# DM1092_Connector.net
KiCad netlist of a schematic drawn in Altium Designer
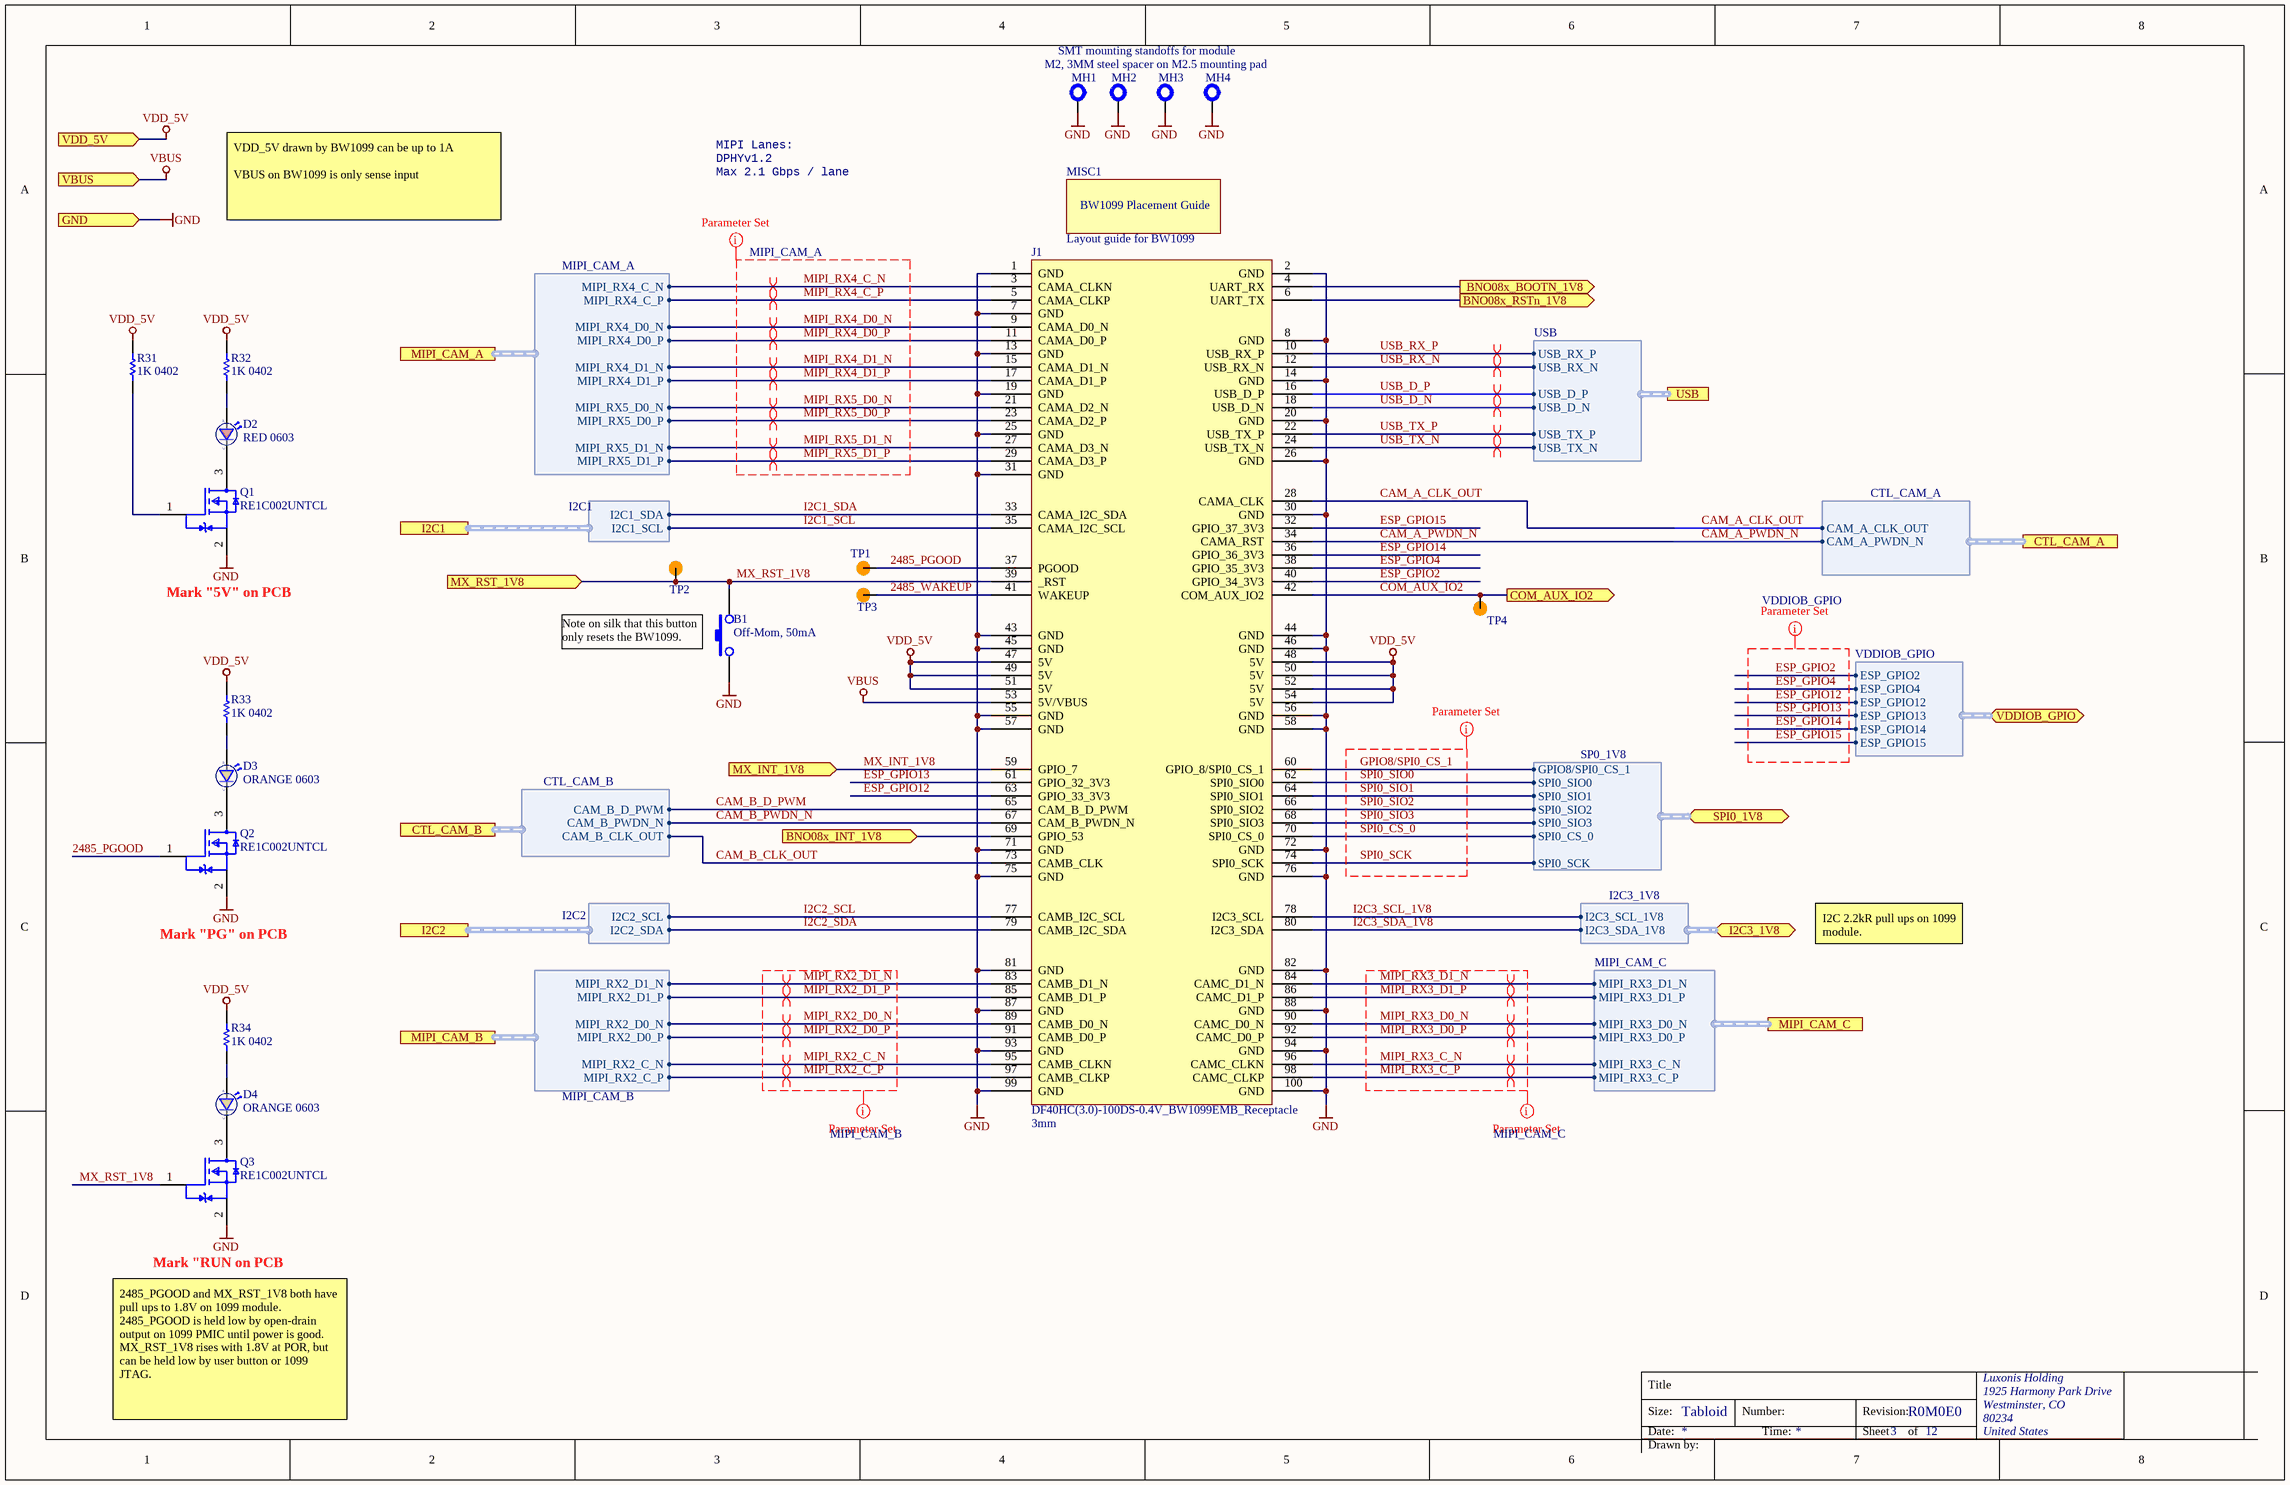
[diagram p0: DM1092_Connector.SchDoc]

(export (version "E")
  (design (tool "Eeschema 10.0.6"))
  (components
    (comp (ref "B1")
      (value "Off-Mom, 50mA")
      (footprint "LuxonisMaster:DTSM-32N-V")
      (description "SWITCH TACTILE SMT 3.5mm * 6mm , brown 160gf")
      (libsource (lib "LuxonisMaster") (part "DTSM-32N-V"))
    )
    (comp (ref "D2")
      (value "RED 0603")
      (footprint "LuxonisMaster:SML_D1xx8W")
      (description "LED RED DIFFUSED 0603 SMD Red 620nm LED Indication - Discrete 2.2V 0603 (1608 Metric)")
      (libsource (lib "LuxonisMaster") (part "SML-D12U8WT86"))
    )
    (comp (ref "D3")
      (value "ORANGE 0603")
      (footprint "LuxonisMaster:SML_D1xx8W")
      (description "LED ORANGE DIFFUSED 0603 SMD Orange 605nm LED Indication - Discrete 2.2V 0603 (1608 Metric)")
      (libsource (lib "LuxonisMaster") (part "SML-D12D8WT86"))
    )
    (comp (ref "D4")
      (value "ORANGE 0603")
      (footprint "LuxonisMaster:SML_D1xx8W")
      (description "LED ORANGE DIFFUSED 0603 SMD Orange 605nm LED Indication - Discrete 2.2V 0603 (1608 Metric)")
      (libsource (lib "LuxonisMaster") (part "SML-D12D8WT86"))
    )
    (comp (ref "J1")
      (value "DF40HC(3.0)-100DS-0.4V_BW1099EMB_Receptacle")
      (footprint "LuxonisMaster:DF40HC-3.0-100DS-0.4V_minpad")
      (description "CONN RCPT 100POS 0.4MM SMD GOLD EMB PINOUT")
      (fields (field (name "MATED STACKING HEIGHT") "3mm"))
      (libsource (lib "BW1098EMB_R0M0E0") (part "DF40HC(3.0)-100DS-0.4V_BW1099EMB"))
    )
    (comp (ref "MH1")
      (value "M2, 3MM steel spacer on M2.5 mounting pad")
      (footprint "LuxonisMaster:9774030243R")
      (description "MP ROUND STANDOFF M2X0.4 STEEL 3MM")
      (libsource (lib "LuxonisMaster") (part "9774030243R"))
    )
    (comp (ref "MH2")
      (value "M2, 3MM steel spacer on M2.5 mounting pad")
      (footprint "LuxonisMaster:9774030243R")
      (description "MP ROUND STANDOFF M2X0.4 STEEL 3MM")
      (libsource (lib "LuxonisMaster") (part "9774030243R"))
    )
    (comp (ref "MH3")
      (value "M2, 3MM steel spacer on M2.5 mounting pad")
      (footprint "LuxonisMaster:9774030243R")
      (description "MP ROUND STANDOFF M2X0.4 STEEL 3MM")
      (libsource (lib "LuxonisMaster") (part "9774030243R"))
    )
    (comp (ref "MH4")
      (value "M2, 3MM steel spacer on M2.5 mounting pad")
      (footprint "LuxonisMaster:9774030243R")
      (description "MP ROUND STANDOFF M2X0.4 STEEL 3MM")
      (libsource (lib "LuxonisMaster") (part "9774030243R"))
    )
    (comp (ref "MISC1")
      (value "Layout guide for BW1099")
      (footprint "BW1099_R3_KTHSNF_Footprint")
      (description "MISC - Use for aligning BW1099 mount")
      (libsource (lib "LuxonisMaster") (part "BW1099_Footprint"))
    )
    (comp (ref "Q1")
      (value "RE1C002UNTCL")
      (footprint "LuxonisMaster:RE1C002UNTCL")
      (description "MOSFET N-CH 20V 0.2A EMT3")
      (libsource (lib "LuxonisMaster") (part "RE1C002UNTCL"))
    )
    (comp (ref "Q2")
      (value "RE1C002UNTCL")
      (footprint "LuxonisMaster:RE1C002UNTCL")
      (description "MOSFET N-CH 20V 0.2A EMT3")
      (libsource (lib "LuxonisMaster") (part "RE1C002UNTCL"))
    )
    (comp (ref "Q3")
      (value "RE1C002UNTCL")
      (footprint "LuxonisMaster:RE1C002UNTCL")
      (description "MOSFET N-CH 20V 0.2A EMT3")
      (libsource (lib "LuxonisMaster") (part "RE1C002UNTCL"))
    )
    (comp (ref "R31")
      (value "1K 0402")
      (footprint "RES_Altium_Vault_Generic:RESC0402(1005)_L")
      (fields (field (name "TOLERANCE") "1%"))
      (libsource (lib "LuxonisMaster") (part "RC0402FR-071KL"))
    )
    (comp (ref "R32")
      (value "1K 0402")
      (footprint "RES_Altium_Vault_Generic:RESC0402(1005)_L")
      (fields (field (name "TOLERANCE") "1%"))
      (libsource (lib "LuxonisMaster") (part "RC0402FR-071KL"))
    )
    (comp (ref "R33")
      (value "1K 0402")
      (footprint "RES_Altium_Vault_Generic:RESC0402(1005)_L")
      (fields (field (name "TOLERANCE") "1%"))
      (libsource (lib "LuxonisMaster") (part "RC0402FR-071KL"))
    )
    (comp (ref "R34")
      (value "1K 0402")
      (footprint "RES_Altium_Vault_Generic:RESC0402(1005)_L")
      (fields (field (name "TOLERANCE") "1%"))
      (libsource (lib "LuxonisMaster") (part "RC0402FR-071KL"))
    )
    (comp (ref "TP1")
      (value "TP100_200_NS")
      (footprint "LuxonisMaster:TP100_200_NS")
      (libsource (lib "LuxonisMaster") (part "TEST_POINT"))
    )
    (comp (ref "TP2")
      (value "TP100_200_NS")
      (footprint "LuxonisMaster:TP100_200_NS")
      (libsource (lib "LuxonisMaster") (part "TEST_POINT"))
    )
    (comp (ref "TP3")
      (value "TP100_200_NS")
      (footprint "LuxonisMaster:TP100_200_NS")
      (libsource (lib "LuxonisMaster") (part "TEST_POINT"))
    )
    (comp (ref "TP4")
      (value "TP100_200_NS")
      (footprint "LuxonisMaster:TP100_200_NS")
      (libsource (lib "LuxonisMaster") (part "TEST_POINT"))
    )
  )
  (nets
    (net (code "12") (name "/2485_PGOOD") (class "Default")
      (node (ref "J1") (pin "37") (pinfunction "PGOOD_37") (pintype "passive"))
      (node (ref "Q2") (pin "1") (pinfunction "Gate_1") (pintype "passive"))
      (node (ref "TP1") (pin "1") (pintype "passive"))
    )
    (net (code "13") (name "/2485_WAKEUP") (class "Default")
      (node (ref "J1") (pin "41") (pinfunction "WAKEUP_41") (pintype "passive"))
      (node (ref "TP3") (pin "1") (pintype "passive"))
    )
    (net (code "14") (name "/BNO08x_BOOTN_1V8") (class "Default")
      (node (ref "J1") (pin "4") (pinfunction "UART_RX_4") (pintype "passive"))
    )
    (net (code "15") (name "/BNO08x_INT_1V8") (class "Default")
      (node (ref "J1") (pin "69") (pinfunction "GPIO_53_69") (pintype "passive"))
    )
    (net (code "16") (name "/BNO08x_RSTn_1V8") (class "Default")
      (node (ref "J1") (pin "6") (pinfunction "UART_TX_6") (pintype "passive"))
    )
    (net (code "17") (name "/CAM_A_CLK_OUT") (class "Default")
      (node (ref "J1") (pin "28") (pinfunction "CAMA_CLK_28") (pintype "passive"))
    )
    (net (code "18") (name "/CAM_A_PWDN_N") (class "Default")
      (node (ref "J1") (pin "34") (pinfunction "CAMA_RST_34") (pintype "passive"))
    )
    (net (code "19") (name "/CAM_B_CLK_OUT") (class "Default")
      (node (ref "J1") (pin "73") (pinfunction "CAMB_CLK_73") (pintype "passive"))
    )
    (net (code "20") (name "/CAM_B_D_PWM") (class "Default")
      (node (ref "J1") (pin "65") (pinfunction "CAM_B_D_PWM_65") (pintype "passive"))
    )
    (net (code "21") (name "/CAM_B_PWDN_N") (class "Default")
      (node (ref "J1") (pin "67") (pinfunction "CAM_B_PWDN_N_67") (pintype "passive"))
    )
    (net (code "22") (name "/COM_AUX_IO2") (class "Default")
      (node (ref "J1") (pin "42") (pinfunction "COM_AUX_IO2_42") (pintype "passive"))
      (node (ref "TP4") (pin "1") (pintype "passive"))
    )
    (net (code "23") (name "/ESP_GPIO2") (class "Default")
      (node (ref "J1") (pin "40") (pinfunction "GPIO_34_3V3_40") (pintype "passive"))
    )
    (net (code "24") (name "/ESP_GPIO4") (class "Default")
      (node (ref "J1") (pin "38") (pinfunction "GPIO_35_3V3_38") (pintype "passive"))
    )
    (net (code "25") (name "/ESP_GPIO12") (class "Default")
      (node (ref "J1") (pin "63") (pinfunction "GPIO_33_3V3_63") (pintype "passive"))
    )
    (net (code "26") (name "/ESP_GPIO13") (class "Default")
      (node (ref "J1") (pin "61") (pinfunction "GPIO_32_3V3_61") (pintype "passive"))
    )
    (net (code "27") (name "/ESP_GPIO14") (class "Default")
      (node (ref "J1") (pin "36") (pinfunction "GPIO_36_3V3_36") (pintype "passive"))
    )
    (net (code "28") (name "/ESP_GPIO15") (class "Default")
      (node (ref "J1") (pin "32") (pinfunction "GPIO_37_3V3_32") (pintype "passive"))
    )
    (net (code "29") (name "/GPIO8{slash}SPI0_CS_1") (class "Default")
      (node (ref "J1") (pin "60") (pinfunction "GPIO_8/SPI0_CS_1_60") (pintype "passive"))
    )
    (net (code "30") (name "/I2C1_SCL") (class "Default")
      (node (ref "J1") (pin "35") (pinfunction "CAMA_I2C_SCL_35") (pintype "passive"))
    )
    (net (code "31") (name "/I2C1_SDA") (class "Default")
      (node (ref "J1") (pin "33") (pinfunction "CAMA_I2C_SDA_33") (pintype "passive"))
    )
    (net (code "32") (name "/I2C2_SCL") (class "Default")
      (node (ref "J1") (pin "77") (pinfunction "CAMB_I2C_SCL_77") (pintype "passive"))
    )
    (net (code "33") (name "/I2C2_SDA") (class "Default")
      (node (ref "J1") (pin "79") (pinfunction "CAMB_I2C_SDA_79") (pintype "passive"))
    )
    (net (code "34") (name "/I2C3_SCL_1V8") (class "Default")
      (node (ref "J1") (pin "78") (pinfunction "I2C3_SCL_78") (pintype "passive"))
    )
    (net (code "35") (name "/I2C3_SDA_1V8") (class "Default")
      (node (ref "J1") (pin "80") (pinfunction "I2C3_SDA_80") (pintype "passive"))
    )
    (net (code "36") (name "/MIPI_RX2_C_N") (class "Default")
      (node (ref "J1") (pin "95") (pinfunction "CAMB_CLKN_95") (pintype "passive"))
    )
    (net (code "37") (name "/MIPI_RX2_C_P") (class "Default")
      (node (ref "J1") (pin "97") (pinfunction "CAMB_CLKP_97") (pintype "passive"))
    )
    (net (code "38") (name "/MIPI_RX2_D0_N") (class "Default")
      (node (ref "J1") (pin "89") (pinfunction "CAMB_D0_N_89") (pintype "passive"))
    )
    (net (code "39") (name "/MIPI_RX2_D0_P") (class "Default")
      (node (ref "J1") (pin "91") (pinfunction "CAMB_D0_P_91") (pintype "passive"))
    )
    (net (code "40") (name "/MIPI_RX2_D1_N") (class "Default")
      (node (ref "J1") (pin "83") (pinfunction "CAMB_D1_N_83") (pintype "passive"))
    )
    (net (code "41") (name "/MIPI_RX2_D1_P") (class "Default")
      (node (ref "J1") (pin "85") (pinfunction "CAMB_D1_P_85") (pintype "passive"))
    )
    (net (code "42") (name "/MIPI_RX3_C_N") (class "Default")
      (node (ref "J1") (pin "96") (pinfunction "CAMC_CLKN_96") (pintype "passive"))
    )
    (net (code "43") (name "/MIPI_RX3_C_P") (class "Default")
      (node (ref "J1") (pin "98") (pinfunction "CAMC_CLKP_98") (pintype "passive"))
    )
    (net (code "44") (name "/MIPI_RX3_D0_N") (class "Default")
      (node (ref "J1") (pin "90") (pinfunction "CAMC_D0_N_90") (pintype "passive"))
    )
    (net (code "45") (name "/MIPI_RX3_D0_P") (class "Default")
      (node (ref "J1") (pin "92") (pinfunction "CAMC_D0_P_92") (pintype "passive"))
    )
    (net (code "46") (name "/MIPI_RX3_D1_N") (class "Default")
      (node (ref "J1") (pin "84") (pinfunction "CAMC_D1_N_84") (pintype "passive"))
    )
    (net (code "47") (name "/MIPI_RX3_D1_P") (class "Default")
      (node (ref "J1") (pin "86") (pinfunction "CAMC_D1_P_86") (pintype "passive"))
    )
    (net (code "48") (name "/MIPI_RX4_C_N") (class "Default")
      (node (ref "J1") (pin "3") (pinfunction "CAMA_CLKN_3") (pintype "passive"))
    )
    (net (code "49") (name "/MIPI_RX4_C_P") (class "Default")
      (node (ref "J1") (pin "5") (pinfunction "CAMA_CLKP_5") (pintype "passive"))
    )
    (net (code "50") (name "/MIPI_RX4_D0_N") (class "Default")
      (node (ref "J1") (pin "9") (pinfunction "CAMA_D0_N_9") (pintype "passive"))
    )
    (net (code "51") (name "/MIPI_RX4_D0_P") (class "Default")
      (node (ref "J1") (pin "11") (pinfunction "CAMA_D0_P_11") (pintype "passive"))
    )
    (net (code "52") (name "/MIPI_RX4_D1_N") (class "Default")
      (node (ref "J1") (pin "15") (pinfunction "CAMA_D1_N_15") (pintype "passive"))
    )
    (net (code "53") (name "/MIPI_RX4_D1_P") (class "Default")
      (node (ref "J1") (pin "17") (pinfunction "CAMA_D1_P_17") (pintype "passive"))
    )
    (net (code "54") (name "/MIPI_RX5_D0_N") (class "Default")
      (node (ref "J1") (pin "21") (pinfunction "CAMA_D2_N_21") (pintype "passive"))
    )
    (net (code "55") (name "/MIPI_RX5_D0_P") (class "Default")
      (node (ref "J1") (pin "23") (pinfunction "CAMA_D2_P_23") (pintype "passive"))
    )
    (net (code "56") (name "/MIPI_RX5_D1_N") (class "Default")
      (node (ref "J1") (pin "27") (pinfunction "CAMA_D3_N_27") (pintype "passive"))
    )
    (net (code "57") (name "/MIPI_RX5_D1_P") (class "Default")
      (node (ref "J1") (pin "29") (pinfunction "CAMA_D3_P_29") (pintype "passive"))
    )
    (net (code "58") (name "/MX_INT_1V8") (class "Default")
      (node (ref "J1") (pin "59") (pinfunction "GPIO_7_59") (pintype "passive"))
    )
    (net (code "59") (name "/MX_RST_1V8") (class "Default")
      (node (ref "B1") (pin "2") (pinfunction "2_2") (pintype "passive"))
      (node (ref "J1") (pin "39") (pinfunction "_RST_39") (pintype "passive"))
      (node (ref "Q3") (pin "1") (pinfunction "Gate_1") (pintype "passive"))
      (node (ref "TP2") (pin "1") (pintype "passive"))
    )
    (net (code "60") (name "/SPI0_CS_0") (class "Default")
      (node (ref "J1") (pin "70") (pinfunction "SPI0_CS_0_70") (pintype "passive"))
    )
    (net (code "61") (name "/SPI0_SCK") (class "Default")
      (node (ref "J1") (pin "74") (pinfunction "SPI0_SCK_74") (pintype "passive"))
    )
    (net (code "62") (name "/SPI0_SIO0") (class "Default")
      (node (ref "J1") (pin "62") (pinfunction "SPI0_SIO0_62") (pintype "passive"))
    )
    (net (code "63") (name "/SPI0_SIO1") (class "Default")
      (node (ref "J1") (pin "64") (pinfunction "SPI0_SIO1_64") (pintype "passive"))
    )
    (net (code "64") (name "/SPI0_SIO2") (class "Default")
      (node (ref "J1") (pin "66") (pinfunction "SPI0_SIO2_66") (pintype "passive"))
    )
    (net (code "65") (name "/SPI0_SIO3") (class "Default")
      (node (ref "J1") (pin "68") (pinfunction "SPI0_SIO3_68") (pintype "passive"))
    )
    (net (code "66") (name "/USB_D_N") (class "Default")
      (node (ref "J1") (pin "18") (pinfunction "USB_D_N_18") (pintype "passive"))
    )
    (net (code "67") (name "/USB_D_P") (class "Default")
      (node (ref "J1") (pin "16") (pinfunction "USB_D_P_16") (pintype "passive"))
    )
    (net (code "68") (name "/USB_RX_N") (class "Default")
      (node (ref "J1") (pin "12") (pinfunction "USB_RX_N_12") (pintype "passive"))
    )
    (net (code "69") (name "/USB_RX_P") (class "Default")
      (node (ref "J1") (pin "10") (pinfunction "USB_RX_P_10") (pintype "passive"))
    )
    (net (code "70") (name "/USB_TX_N") (class "Default")
      (node (ref "J1") (pin "24") (pinfunction "USB_TX_N_24") (pintype "passive"))
    )
    (net (code "71") (name "/USB_TX_P") (class "Default")
      (node (ref "J1") (pin "22") (pinfunction "USB_TX_P_22") (pintype "passive"))
    )
    (net (code "83") (name "GND") (class "Default")
      (node (ref "B1") (pin "1") (pinfunction "1_1") (pintype "passive"))
      (node (ref "J1") (pin "1") (pinfunction "GND_1") (pintype "passive"))
      (node (ref "J1") (pin "100") (pinfunction "GND_100") (pintype "passive"))
      (node (ref "J1") (pin "13") (pinfunction "GND_13") (pintype "passive"))
      (node (ref "J1") (pin "14") (pinfunction "GND_14") (pintype "passive"))
      (node (ref "J1") (pin "19") (pinfunction "GND_19") (pintype "passive"))
      (node (ref "J1") (pin "2") (pinfunction "GND_2") (pintype "passive"))
      (node (ref "J1") (pin "20") (pinfunction "GND_20") (pintype "passive"))
      (node (ref "J1") (pin "25") (pinfunction "GND_25") (pintype "passive"))
      (node (ref "J1") (pin "26") (pinfunction "GND_26") (pintype "passive"))
      (node (ref "J1") (pin "30") (pinfunction "GND_30") (pintype "passive"))
      (node (ref "J1") (pin "31") (pinfunction "GND_31") (pintype "passive"))
      (node (ref "J1") (pin "43") (pinfunction "GND_43") (pintype "passive"))
      (node (ref "J1") (pin "44") (pinfunction "GND_44") (pintype "passive"))
      (node (ref "J1") (pin "45") (pinfunction "GND_45") (pintype "passive"))
      (node (ref "J1") (pin "46") (pinfunction "GND_46") (pintype "passive"))
      (node (ref "J1") (pin "55") (pinfunction "GND_55") (pintype "passive"))
      (node (ref "J1") (pin "56") (pinfunction "GND_56") (pintype "passive"))
      (node (ref "J1") (pin "57") (pinfunction "GND_57") (pintype "passive"))
      (node (ref "J1") (pin "58") (pinfunction "GND_58") (pintype "passive"))
      (node (ref "J1") (pin "7") (pinfunction "GND_7") (pintype "passive"))
      (node (ref "J1") (pin "71") (pinfunction "GND_71") (pintype "passive"))
      (node (ref "J1") (pin "72") (pinfunction "GND_72") (pintype "passive"))
      (node (ref "J1") (pin "75") (pinfunction "GND_75") (pintype "passive"))
      (node (ref "J1") (pin "76") (pinfunction "GND_76") (pintype "passive"))
      (node (ref "J1") (pin "8") (pinfunction "GND_8") (pintype "passive"))
      (node (ref "J1") (pin "81") (pinfunction "GND_81") (pintype "passive"))
      (node (ref "J1") (pin "82") (pinfunction "GND_82") (pintype "passive"))
      (node (ref "J1") (pin "87") (pinfunction "GND_87") (pintype "passive"))
      (node (ref "J1") (pin "88") (pinfunction "GND_88") (pintype "passive"))
      (node (ref "J1") (pin "93") (pinfunction "GND_93") (pintype "passive"))
      (node (ref "J1") (pin "94") (pinfunction "GND_94") (pintype "passive"))
      (node (ref "J1") (pin "99") (pinfunction "GND_99") (pintype "passive"))
      (node (ref "MH1") (pin "1") (pintype "passive"))
      (node (ref "MH2") (pin "1") (pintype "passive"))
      (node (ref "MH3") (pin "1") (pintype "passive"))
      (node (ref "MH4") (pin "1") (pintype "passive"))
      (node (ref "Q1") (pin "2") (pinfunction "Source_2") (pintype "passive"))
      (node (ref "Q2") (pin "2") (pinfunction "Source_2") (pintype "passive"))
      (node (ref "Q3") (pin "2") (pinfunction "Source_2") (pintype "passive"))
    )
    (net (code "84") (name "Net-(D2-A)") (class "Default")
      (node (ref "D2") (pin "2") (pinfunction "A_2") (pintype "passive"))
      (node (ref "R32") (pin "1") (pinfunction "1_1") (pintype "passive"))
    )
    (net (code "85") (name "Net-(D2-C)") (class "Default")
      (node (ref "D2") (pin "1") (pinfunction "C_1") (pintype "passive"))
      (node (ref "Q1") (pin "3") (pinfunction "Drain_3") (pintype "passive"))
    )
    (net (code "86") (name "Net-(D3-A)") (class "Default")
      (node (ref "D3") (pin "2") (pinfunction "A_2") (pintype "passive"))
      (node (ref "R33") (pin "1") (pinfunction "1_1") (pintype "passive"))
    )
    (net (code "87") (name "Net-(D3-C)") (class "Default")
      (node (ref "D3") (pin "1") (pinfunction "C_1") (pintype "passive"))
      (node (ref "Q2") (pin "3") (pinfunction "Drain_3") (pintype "passive"))
    )
    (net (code "88") (name "Net-(D4-A)") (class "Default")
      (node (ref "D4") (pin "2") (pinfunction "A_2") (pintype "passive"))
      (node (ref "R34") (pin "1") (pinfunction "1_1") (pintype "passive"))
    )
    (net (code "89") (name "Net-(D4-C)") (class "Default")
      (node (ref "D4") (pin "1") (pinfunction "C_1") (pintype "passive"))
      (node (ref "Q3") (pin "3") (pinfunction "Drain_3") (pintype "passive"))
    )
    (net (code "90") (name "Net-(Q1-Gate)") (class "Default")
      (node (ref "Q1") (pin "1") (pinfunction "Gate_1") (pintype "passive"))
      (node (ref "R31") (pin "1") (pinfunction "1_1") (pintype "passive"))
    )
    (net (code "91") (name "VBUS") (class "Default")
      (node (ref "J1") (pin "53") (pinfunction "5V/VBUS_53") (pintype "passive"))
    )
    (net (code "92") (name "VDD_5V") (class "Default")
      (node (ref "J1") (pin "47") (pinfunction "5V_47") (pintype "passive"))
      (node (ref "J1") (pin "48") (pinfunction "5V_48") (pintype "passive"))
      (node (ref "J1") (pin "49") (pinfunction "5V_49") (pintype "passive"))
      (node (ref "J1") (pin "50") (pinfunction "5V_50") (pintype "passive"))
      (node (ref "J1") (pin "51") (pinfunction "5V_51") (pintype "passive"))
      (node (ref "J1") (pin "52") (pinfunction "5V_52") (pintype "passive"))
      (node (ref "J1") (pin "54") (pinfunction "5V_54") (pintype "passive"))
      (node (ref "R31") (pin "2") (pinfunction "2_2") (pintype "passive"))
      (node (ref "R32") (pin "2") (pinfunction "2_2") (pintype "passive"))
      (node (ref "R33") (pin "2") (pinfunction "2_2") (pintype "passive"))
      (node (ref "R34") (pin "2") (pinfunction "2_2") (pintype "passive"))
    )
  )
)
